# L_ftung_230217.net
KiCad netlist of a schematic drawn in EAGLE
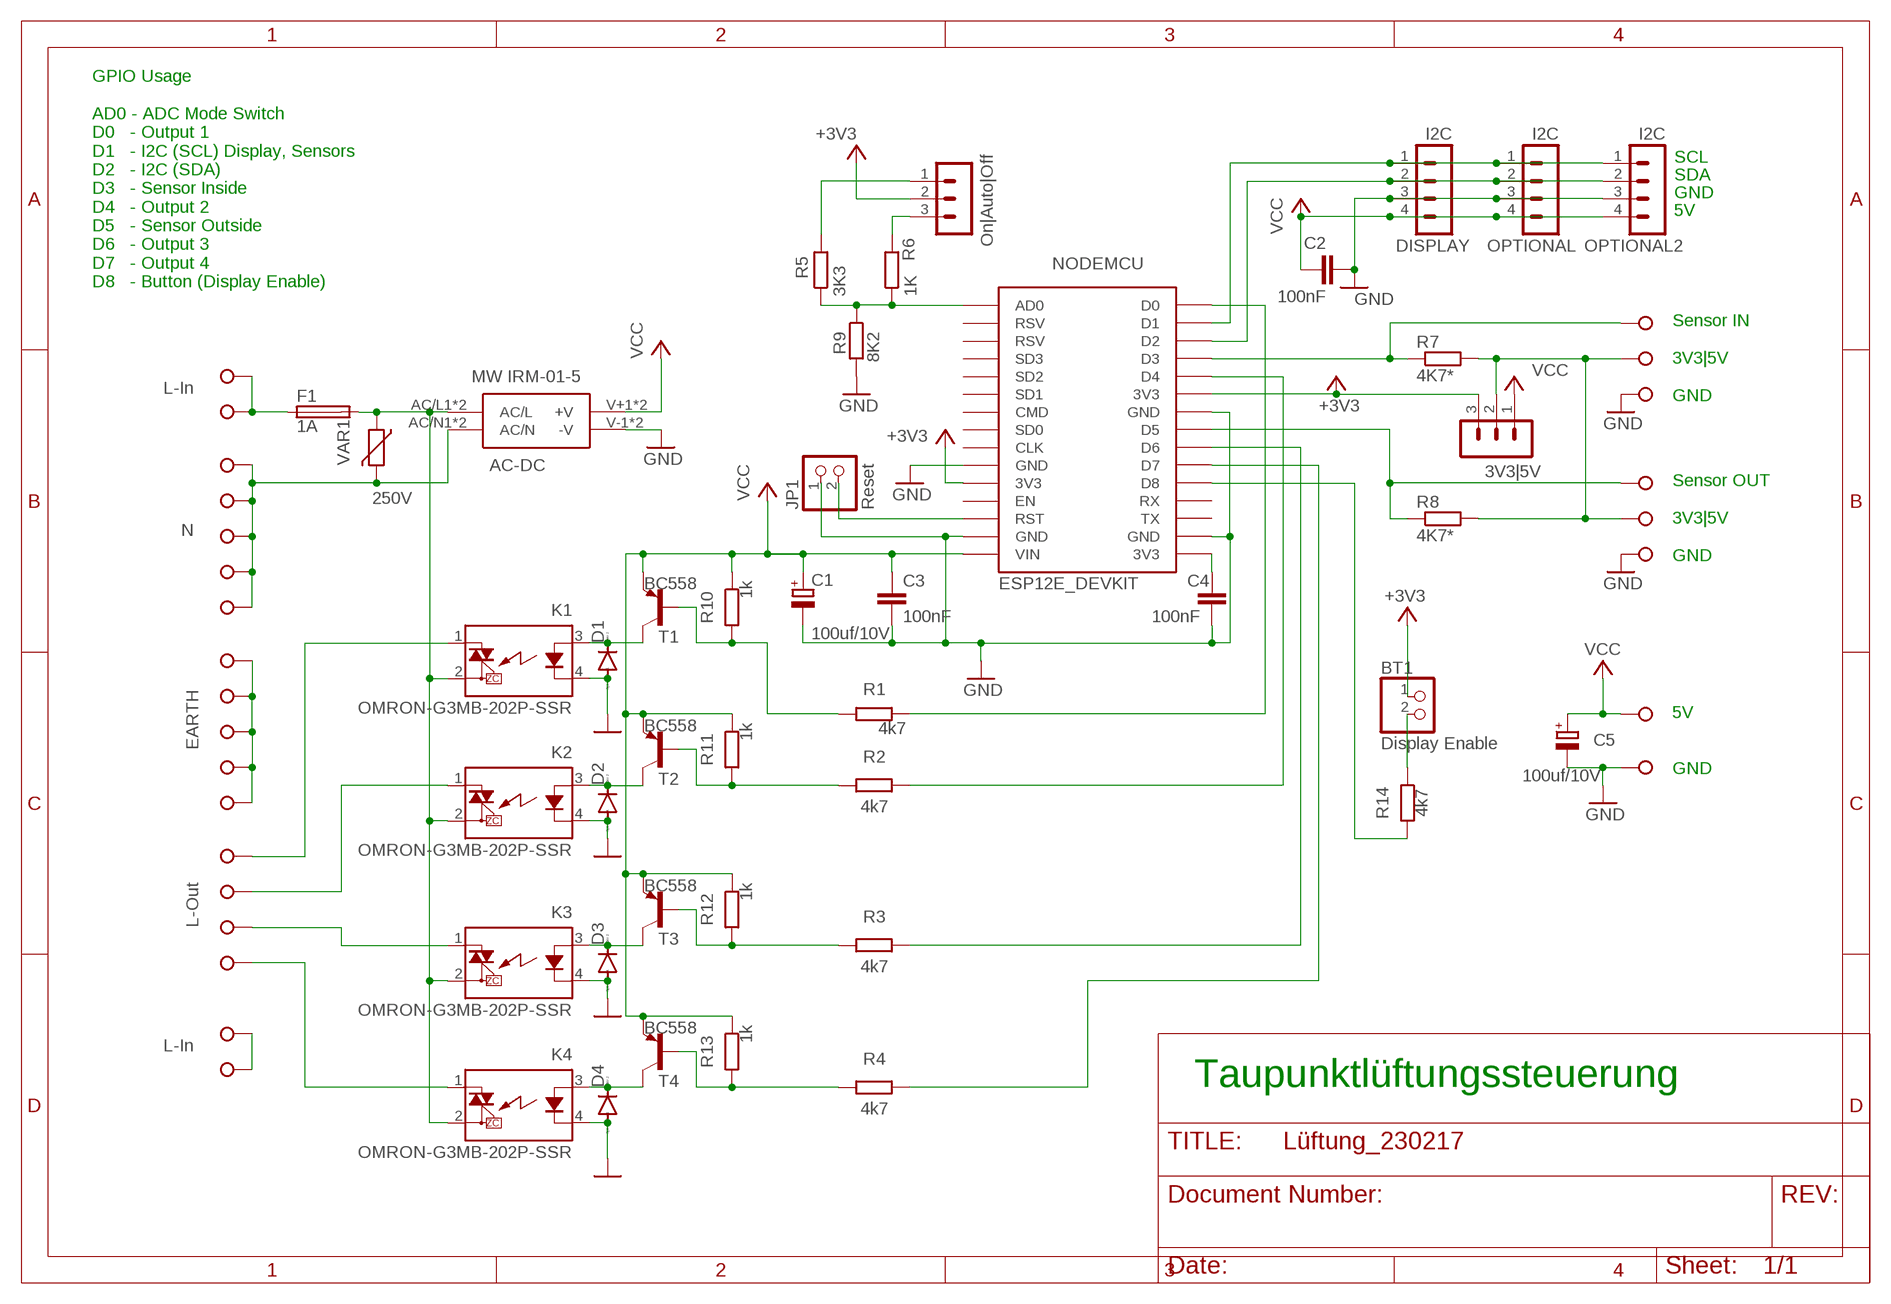
[diagram p0: schematic, sheet 1]

(export (version "E")
  (design (tool "Eeschema 10.0.6"))
  (components
    (comp (ref "5V|3V3")
      (value "3V3|5V")
      (footprint "eagle-import:LüFTUNG_230217_2_CON-LSTB_MA03-1")
      (libsource (lib "eagle-import") (part "LüFTUNG_230217_2_CON-LSTB_MA03-1"))
    )
    (comp (ref "AC-DC")
      (value "MW IRM-01-5")
      (footprint "eagle-import:LüFTUNG_230217_2_SAMACSYS_PARTS_IRM015")
      (fields
        (field (name "MANUFACTURER_PART_NUMBER") "IRM-01-5")
        (field (name "MOUSER_PART_NUMBER") "709-IRM01-5")
      )
      (libsource (lib "eagle-import") (part "LüFTUNG_230217_2_SAMACSYS_PARTS_IRM-01-5"))
    )
    (comp (ref "BT1")
      (value "Display Enable")
      (footprint "eagle-import:LüFTUNG_230217_2_PINHEAD_1X02")
      (libsource (lib "eagle-import") (part "LüFTUNG_230217_2_PINHEAD_PINHD-1X2"))
    )
    (comp (ref "C1")
      (value "100uf/10V")
      (footprint "eagle-import:LüFTUNG_230217_2_MY_RCL_E2,5-7")
      (libsource (lib "eagle-import") (part "LüFTUNG_230217_2_MY_RCL_CPOL-EUE2.5-7"))
    )
    (comp (ref "C2")
      (value "100nF")
      (footprint "eagle-import:LüFTUNG_230217_2_CAPACITOR-WIMA_C5B3.5")
      (libsource (lib "eagle-import") (part "LüFTUNG_230217_2_CAPACITOR-WIMA_C5/3.5"))
    )
    (comp (ref "C3")
      (value "100nF")
      (footprint "eagle-import:LüFTUNG_230217_2_CAPACITOR-WIMA_C5B3.5")
      (libsource (lib "eagle-import") (part "LüFTUNG_230217_2_CAPACITOR-WIMA_C5/3.5"))
    )
    (comp (ref "C4")
      (value "100nF")
      (footprint "eagle-import:LüFTUNG_230217_2_CAPACITOR-WIMA_C5B3.5")
      (libsource (lib "eagle-import") (part "LüFTUNG_230217_2_CAPACITOR-WIMA_C5/3.5"))
    )
    (comp (ref "C5")
      (value "100uf/10V")
      (footprint "eagle-import:LüFTUNG_230217_2_MY_RCL_E2,5-7")
      (libsource (lib "eagle-import") (part "LüFTUNG_230217_2_MY_RCL_CPOL-EUE2.5-7"))
    )
    (comp (ref "D1")
      (value "LüFTUNG_230217_2_DIODE_1N4148")
      (footprint "eagle-import:LüFTUNG_230217_2_DIODE_D-5")
      (libsource (lib "eagle-import") (part "LüFTUNG_230217_2_DIODE_1N4148"))
    )
    (comp (ref "D2")
      (value "LüFTUNG_230217_2_DIODE_1N4148DO35-7")
      (footprint "eagle-import:LüFTUNG_230217_2_DIODE_DO35-7")
      (libsource (lib "eagle-import") (part "LüFTUNG_230217_2_DIODE_1N4148DO35-7"))
    )
    (comp (ref "D3")
      (value "LüFTUNG_230217_2_DIODE_1N4148DO35-7")
      (footprint "eagle-import:LüFTUNG_230217_2_DIODE_DO35-7")
      (libsource (lib "eagle-import") (part "LüFTUNG_230217_2_DIODE_1N4148DO35-7"))
    )
    (comp (ref "D4")
      (value "LüFTUNG_230217_2_DIODE_1N4148DO35-7")
      (footprint "eagle-import:LüFTUNG_230217_2_DIODE_DO35-7")
      (libsource (lib "eagle-import") (part "LüFTUNG_230217_2_DIODE_1N4148DO35-7"))
    )
    (comp (ref "DISPLAY")
      (value "I2C")
      (footprint "eagle-import:LüFTUNG_230217_2_CON-LSTB_MA04-1")
      (libsource (lib "eagle-import") (part "LüFTUNG_230217_2_CON-LSTB_MA04-1"))
    )
    (comp (ref "F1")
      (value "1A")
      (footprint "eagle-import:LüFTUNG_230217_2_MY_FUSE_SH22,5")
      (libsource (lib "eagle-import") (part "LüFTUNG_230217_2_MY_FUSE_FUSESH22,5"))
    )
    (comp (ref "JP1")
      (value "Reset")
      (footprint "eagle-import:LüFTUNG_230217_2_PINHEAD_1X02")
      (libsource (lib "eagle-import") (part "LüFTUNG_230217_2_PINHEAD_PINHD-1X2"))
    )
    (comp (ref "K1")
      (value "OMRON-G3MB-202P-SSR")
      (footprint "eagle-import:LüFTUNG_230217_2_OMRON-G3MB-202P-SSR_OMRON-G3MB-202P-SSR")
      (libsource (lib "eagle-import") (part "LüFTUNG_230217_2_OMRON-G3MB-202P-SSR_OMRON-G3MB-202P-SSR"))
    )
    (comp (ref "K2")
      (value "OMRON-G3MB-202P-SSR")
      (footprint "eagle-import:LüFTUNG_230217_2_OMRON-G3MB-202P-SSR_OMRON-G3MB-202P-SSR")
      (libsource (lib "eagle-import") (part "LüFTUNG_230217_2_OMRON-G3MB-202P-SSR_OMRON-G3MB-202P-SSR"))
    )
    (comp (ref "K3")
      (value "OMRON-G3MB-202P-SSR")
      (footprint "eagle-import:LüFTUNG_230217_2_OMRON-G3MB-202P-SSR_OMRON-G3MB-202P-SSR")
      (libsource (lib "eagle-import") (part "LüFTUNG_230217_2_OMRON-G3MB-202P-SSR_OMRON-G3MB-202P-SSR"))
    )
    (comp (ref "K4")
      (value "OMRON-G3MB-202P-SSR")
      (footprint "eagle-import:LüFTUNG_230217_2_OMRON-G3MB-202P-SSR_OMRON-G3MB-202P-SSR")
      (libsource (lib "eagle-import") (part "LüFTUNG_230217_2_OMRON-G3MB-202P-SSR_OMRON-G3MB-202P-SSR"))
    )
    (comp (ref "NODEMCU")
      (value "ESP12E_DEVKIT")
      (footprint "eagle-import:LüFTUNG_230217_2_ESP12E_DEVKIT_ESP12E_DEVKIT")
      (libsource (lib "eagle-import") (part "LüFTUNG_230217_2_ESP12E_DEVKIT_ESP12E_DEVKIT"))
    )
    (comp (ref "OPTIONAL")
      (value "I2C")
      (footprint "eagle-import:LüFTUNG_230217_2_CON-LSTB_MA04-1")
      (libsource (lib "eagle-import") (part "LüFTUNG_230217_2_CON-LSTB_MA04-1"))
    )
    (comp (ref "OPTIONAL2")
      (value "I2C")
      (footprint "eagle-import:LüFTUNG_230217_2_CON-LSTB_MA04-1")
      (libsource (lib "eagle-import") (part "LüFTUNG_230217_2_CON-LSTB_MA04-1"))
    )
    (comp (ref "R1")
      (value "4k7")
      (footprint "eagle-import:LüFTUNG_230217_2_MY_RCL_0207_10")
      (libsource (lib "eagle-import") (part "LüFTUNG_230217_2_MY_RCL_R-EU_0207/10"))
    )
    (comp (ref "R2")
      (value "4k7")
      (footprint "eagle-import:LüFTUNG_230217_2_MY_RCL_0207_10")
      (libsource (lib "eagle-import") (part "LüFTUNG_230217_2_MY_RCL_R-EU_0207/10"))
    )
    (comp (ref "R3")
      (value "4k7")
      (footprint "eagle-import:LüFTUNG_230217_2_MY_RCL_0207_10")
      (libsource (lib "eagle-import") (part "LüFTUNG_230217_2_MY_RCL_R-EU_0207/10"))
    )
    (comp (ref "R4")
      (value "4k7")
      (footprint "eagle-import:LüFTUNG_230217_2_MY_RCL_0207_10")
      (libsource (lib "eagle-import") (part "LüFTUNG_230217_2_MY_RCL_R-EU_0207/10"))
    )
    (comp (ref "R5")
      (value "3K3")
      (footprint "eagle-import:LüFTUNG_230217_2_MY_RCL_0204V")
      (libsource (lib "eagle-import") (part "LüFTUNG_230217_2_MY_RCL_R-EU_0204/2V"))
    )
    (comp (ref "R6")
      (value "1K")
      (footprint "eagle-import:LüFTUNG_230217_2_MY_RCL_0204V")
      (libsource (lib "eagle-import") (part "LüFTUNG_230217_2_MY_RCL_R-EU_0204/2V"))
    )
    (comp (ref "R7")
      (value "4K7*")
      (footprint "eagle-import:LüFTUNG_230217_2_MY_RCL_0207_10")
      (libsource (lib "eagle-import") (part "LüFTUNG_230217_2_MY_RCL_R-EU_0207/10"))
    )
    (comp (ref "R8")
      (value "4K7*")
      (footprint "eagle-import:LüFTUNG_230217_2_MY_RCL_0207_10")
      (libsource (lib "eagle-import") (part "LüFTUNG_230217_2_MY_RCL_R-EU_0207/10"))
    )
    (comp (ref "R9")
      (value "8K2")
      (footprint "eagle-import:LüFTUNG_230217_2_MY_RCL_0204V")
      (libsource (lib "eagle-import") (part "LüFTUNG_230217_2_MY_RCL_R-EU_0204/2V"))
    )
    (comp (ref "R10")
      (value "1k")
      (footprint "eagle-import:LüFTUNG_230217_2_MY_RCL_0207_10")
      (libsource (lib "eagle-import") (part "LüFTUNG_230217_2_MY_RCL_R-EU_0207/10"))
    )
    (comp (ref "R11")
      (value "1k")
      (footprint "eagle-import:LüFTUNG_230217_2_MY_RCL_0207_10")
      (libsource (lib "eagle-import") (part "LüFTUNG_230217_2_MY_RCL_R-EU_0207/10"))
    )
    (comp (ref "R12")
      (value "1k")
      (footprint "eagle-import:LüFTUNG_230217_2_MY_RCL_0207_10")
      (libsource (lib "eagle-import") (part "LüFTUNG_230217_2_MY_RCL_R-EU_0207/10"))
    )
    (comp (ref "R13")
      (value "1k")
      (footprint "eagle-import:LüFTUNG_230217_2_MY_RCL_0207_10")
      (libsource (lib "eagle-import") (part "LüFTUNG_230217_2_MY_RCL_R-EU_0207/10"))
    )
    (comp (ref "R14")
      (value "4k7")
      (footprint "eagle-import:LüFTUNG_230217_2_MY_RCL_0207_10")
      (libsource (lib "eagle-import") (part "LüFTUNG_230217_2_MY_RCL_R-EU_0207/10"))
    )
    (comp (ref "SWITCH")
      (value "On|Auto|Off")
      (footprint "eagle-import:LüFTUNG_230217_2_CON-LSTB_MA03-1")
      (libsource (lib "eagle-import") (part "LüFTUNG_230217_2_CON-LSTB_MA03-1"))
    )
    (comp (ref "T1")
      (value "BC558")
      (footprint "eagle-import:LüFTUNG_230217_2_TRANSISTOR-NEU-TO92_TO92")
      (libsource (lib "eagle-import") (part "LüFTUNG_230217_2_TRANSISTOR-NEU-TO92_-PNP-TO92"))
    )
    (comp (ref "T2")
      (value "BC558")
      (footprint "eagle-import:LüFTUNG_230217_2_TRANSISTOR-NEU-TO92_TO92")
      (libsource (lib "eagle-import") (part "LüFTUNG_230217_2_TRANSISTOR-NEU-TO92_-PNP-TO92"))
    )
    (comp (ref "T3")
      (value "BC558")
      (footprint "eagle-import:LüFTUNG_230217_2_TRANSISTOR-NEU-TO92_TO92")
      (libsource (lib "eagle-import") (part "LüFTUNG_230217_2_TRANSISTOR-NEU-TO92_-PNP-TO92"))
    )
    (comp (ref "T4")
      (value "BC558")
      (footprint "eagle-import:LüFTUNG_230217_2_TRANSISTOR-NEU-TO92_TO92")
      (libsource (lib "eagle-import") (part "LüFTUNG_230217_2_TRANSISTOR-NEU-TO92_-PNP-TO92"))
    )
    (comp (ref "VAR1")
      (value "250V")
      (footprint "eagle-import:LüFTUNG_230217_2_MY_VARISTOR_R-5")
      (libsource (lib "eagle-import") (part "LüFTUNG_230217_2_MY_VARISTOR_VARISTOR-5"))
    )
    (comp (ref "X1")
      (value "L-In")
      (footprint "eagle-import:CON-WAGO-508_W236-1")
      (libsource (lib "eagle-import") (part "CON-WAGO-508_W236-1"))
    )
    (comp (ref "X2")
      (value "L-In")
      (footprint "eagle-import:CON-WAGO-508_W236-NOCAP")
      (libsource (lib "eagle-import") (part "CON-WAGO-508_W236-1CON-WAGO-508_W236-NOCAP"))
    )
    (comp (ref "X3")
      (value "N")
      (footprint "eagle-import:CON-WAGO-508_W236-1")
      (libsource (lib "eagle-import") (part "CON-WAGO-508_W236-1"))
    )
    (comp (ref "X4")
      (value "N")
      (footprint "eagle-import:CON-WAGO-508_W236-NOCAP")
      (libsource (lib "eagle-import") (part "CON-WAGO-508_W236-1CON-WAGO-508_W236-NOCAP"))
    )
    (comp (ref "X5")
      (value "N")
      (footprint "eagle-import:CON-WAGO-508_W236-NOCAP")
      (libsource (lib "eagle-import") (part "CON-WAGO-508_W236-1CON-WAGO-508_W236-NOCAP"))
    )
    (comp (ref "X6")
      (value "N")
      (footprint "eagle-import:CON-WAGO-508_W236-NOCAP")
      (libsource (lib "eagle-import") (part "CON-WAGO-508_W236-1CON-WAGO-508_W236-NOCAP"))
    )
    (comp (ref "X7")
      (value "N")
      (footprint "eagle-import:CON-WAGO-508_W236-NOCAP")
      (libsource (lib "eagle-import") (part "CON-WAGO-508_W236-1CON-WAGO-508_W236-NOCAP"))
    )
    (comp (ref "X8")
      (value "EARTH")
      (footprint "eagle-import:CON-WAGO-508_W236-1")
      (libsource (lib "eagle-import") (part "CON-WAGO-508_W236-1"))
    )
    (comp (ref "X9")
      (value "EARTH")
      (footprint "eagle-import:CON-WAGO-508_W236-NOCAP")
      (libsource (lib "eagle-import") (part "CON-WAGO-508_W236-1CON-WAGO-508_W236-NOCAP"))
    )
    (comp (ref "X10")
      (value "EARTH")
      (footprint "eagle-import:CON-WAGO-508_W236-NOCAP")
      (libsource (lib "eagle-import") (part "CON-WAGO-508_W236-1CON-WAGO-508_W236-NOCAP"))
    )
    (comp (ref "X11")
      (value "EARTH")
      (footprint "eagle-import:CON-WAGO-508_W236-NOCAP")
      (libsource (lib "eagle-import") (part "CON-WAGO-508_W236-1CON-WAGO-508_W236-NOCAP"))
    )
    (comp (ref "X12")
      (value "EARTH")
      (footprint "eagle-import:CON-WAGO-508_W236-NOCAP")
      (libsource (lib "eagle-import") (part "CON-WAGO-508_W236-1CON-WAGO-508_W236-NOCAP"))
    )
    (comp (ref "X13")
      (value "L-Out")
      (footprint "eagle-import:CON-WAGO-508_W236-1")
      (libsource (lib "eagle-import") (part "CON-WAGO-508_W236-1"))
    )
    (comp (ref "X14")
      (value "L-Out")
      (footprint "eagle-import:CON-WAGO-508_W236-NOCAP")
      (libsource (lib "eagle-import") (part "CON-WAGO-508_W236-1CON-WAGO-508_W236-NOCAP"))
    )
    (comp (ref "X15")
      (value "L-Out")
      (footprint "eagle-import:CON-WAGO-508_W236-NOCAP")
      (libsource (lib "eagle-import") (part "CON-WAGO-508_W236-1CON-WAGO-508_W236-NOCAP"))
    )
    (comp (ref "X16")
      (value "L-Out")
      (footprint "eagle-import:CON-WAGO-508_W236-NOCAP")
      (libsource (lib "eagle-import") (part "CON-WAGO-508_W236-1CON-WAGO-508_W236-NOCAP"))
    )
    (comp (ref "X17")
      (value "L-In")
      (footprint "eagle-import:CON-WAGO-508_W236-NOCAP")
      (libsource (lib "eagle-import") (part "CON-WAGO-508_W236-1CON-WAGO-508_W236-NOCAP"))
    )
    (comp (ref "X18")
      (value "L-In")
      (footprint "eagle-import:CON-WAGO-508_W236-1")
      (libsource (lib "eagle-import") (part "CON-WAGO-508_W236-1"))
    )
    (comp (ref "X19")
      (value "Sensor-In")
      (footprint "eagle-import:CON-WAGO-508_W236-NOCAP")
      (libsource (lib "eagle-import") (part "CON-WAGO-508_W236-1CON-WAGO-508_W236-NOCAP"))
    )
    (comp (ref "X20")
      (value "3V3")
      (footprint "eagle-import:CON-WAGO-508_W236-NOCAP")
      (libsource (lib "eagle-import") (part "CON-WAGO-508_W236-1CON-WAGO-508_W236-NOCAP"))
    )
    (comp (ref "X21")
      (value "GND")
      (footprint "eagle-import:CON-WAGO-508_W236-1")
      (libsource (lib "eagle-import") (part "CON-WAGO-508_W236-1"))
    )
    (comp (ref "X22")
      (value "Sensor-Out")
      (footprint "eagle-import:CON-WAGO-508_W236-NOCAP")
      (libsource (lib "eagle-import") (part "CON-WAGO-508_W236-1CON-WAGO-508_W236-NOCAP"))
    )
    (comp (ref "X23")
      (value "3V3")
      (footprint "eagle-import:CON-WAGO-508_W236-NOCAP")
      (libsource (lib "eagle-import") (part "CON-WAGO-508_W236-1CON-WAGO-508_W236-NOCAP"))
    )
    (comp (ref "X24")
      (value "GND")
      (footprint "eagle-import:CON-WAGO-508_W236-1")
      (libsource (lib "eagle-import") (part "CON-WAGO-508_W236-1"))
    )
    (comp (ref "X25")
      (value "GND")
      (footprint "eagle-import:CON-WAGO-508_W236-NOCAP")
      (libsource (lib "eagle-import") (part "CON-WAGO-508_W236-1CON-WAGO-508_W236-NOCAP"))
    )
    (comp (ref "X26")
      (value "VCC")
      (footprint "eagle-import:CON-WAGO-508_W236-1")
      (libsource (lib "eagle-import") (part "CON-WAGO-508_W236-1"))
    )
  )
  (nets
    (net (code "1") (name "+3V3") (class "Default")
      (node (ref "5V|3V3") (pin "3") (pinfunction "3_3") (pintype "passive"))
      (node (ref "BT1") (pin "1") (pinfunction "1_1") (pintype "passive"))
      (node (ref "NODEMCU") (pin "3V3@0") (pinfunction "3V3_3V3@0") (pintype "bidirectional"))
      (node (ref "NODEMCU") (pin "3V3@1") (pinfunction "3V3_3V3@1") (pintype "bidirectional"))
      (node (ref "SWITCH") (pin "2") (pinfunction "2_2") (pintype "passive"))
    )
    (net (code "2") (name "GND") (class "Default")
      (node (ref "AC-DC") (pin "V-1") (pinfunction "-V_V-1") (pintype "bidirectional"))
      (node (ref "AC-DC") (pin "V-2") (pinfunction "-V_V-2") (pintype "bidirectional"))
      (node (ref "C1") (pin "-") (pinfunction "-_-") (pintype "passive"))
      (node (ref "C2") (pin "2") (pinfunction "2_2") (pintype "passive"))
      (node (ref "C3") (pin "2") (pinfunction "2_2") (pintype "passive"))
      (node (ref "C4") (pin "2") (pinfunction "2_2") (pintype "passive"))
      (node (ref "C5") (pin "-") (pinfunction "-_-") (pintype "passive"))
      (node (ref "D1") (pin "A") (pinfunction "A_A") (pintype "passive"))
      (node (ref "D2") (pin "A") (pinfunction "A_A") (pintype "passive"))
      (node (ref "D3") (pin "A") (pinfunction "A_A") (pintype "passive"))
      (node (ref "D4") (pin "A") (pinfunction "A_A") (pintype "passive"))
      (node (ref "DISPLAY") (pin "3") (pinfunction "3_3") (pintype "passive"))
      (node (ref "JP1") (pin "1") (pinfunction "1_1") (pintype "passive"))
      (node (ref "K1") (pin "4") (pinfunction "K_4") (pintype "passive"))
      (node (ref "K2") (pin "4") (pinfunction "K_4") (pintype "passive"))
      (node (ref "K3") (pin "4") (pinfunction "K_4") (pintype "passive"))
      (node (ref "K4") (pin "4") (pinfunction "K_4") (pintype "passive"))
      (node (ref "NODEMCU") (pin "GND@0") (pinfunction "GND_GND@0") (pintype "bidirectional"))
      (node (ref "NODEMCU") (pin "GND@1") (pinfunction "GND_GND@1") (pintype "bidirectional"))
      (node (ref "NODEMCU") (pin "GND@2") (pinfunction "GND_GND@2") (pintype "bidirectional"))
      (node (ref "NODEMCU") (pin "GND@3") (pinfunction "GND_GND@3") (pintype "bidirectional"))
      (node (ref "OPTIONAL") (pin "3") (pinfunction "3_3") (pintype "passive"))
      (node (ref "OPTIONAL2") (pin "3") (pinfunction "3_3") (pintype "passive"))
      (node (ref "R9") (pin "2") (pinfunction "2_2") (pintype "passive"))
      (node (ref "X21") (pin "1") (pinfunction "KL1_1") (pintype "passive"))
      (node (ref "X21") (pin "2") (pinfunction "KL1_2") (pintype "passive"))
      (node (ref "X24") (pin "1") (pinfunction "KL1_1") (pintype "passive"))
      (node (ref "X24") (pin "2") (pinfunction "KL1_2") (pintype "passive"))
      (node (ref "X25") (pin "1") (pinfunction "KL1_1") (pintype "passive"))
      (node (ref "X25") (pin "2") (pinfunction "KL1_2") (pintype "passive"))
    )
    (net (code "3") (name "Net-(5V|3V3-Pad2)") (class "Default")
      (node (ref "5V|3V3") (pin "2") (pinfunction "2_2") (pintype "passive"))
      (node (ref "R7") (pin "2") (pinfunction "2_2") (pintype "passive"))
      (node (ref "R8") (pin "2") (pinfunction "2_2") (pintype "passive"))
      (node (ref "X20") (pin "1") (pinfunction "KL1_1") (pintype "passive"))
      (node (ref "X20") (pin "2") (pinfunction "KL1_2") (pintype "passive"))
      (node (ref "X23") (pin "1") (pinfunction "KL1_1") (pintype "passive"))
      (node (ref "X23") (pin "2") (pinfunction "KL1_2") (pintype "passive"))
    )
    (net (code "4") (name "Net-(AC-DC-AC{slash}N-PadAC{slash}N1)") (class "Default")
      (node (ref "AC-DC") (pin "AC/N1") (pinfunction "AC/N_AC/N1") (pintype "bidirectional"))
      (node (ref "AC-DC") (pin "AC/N2") (pinfunction "AC/N_AC/N2") (pintype "bidirectional"))
      (node (ref "VAR1") (pin "2") (pinfunction "2_2") (pintype "passive"))
      (node (ref "X3") (pin "1") (pinfunction "KL1_1") (pintype "passive"))
      (node (ref "X3") (pin "2") (pinfunction "KL1_2") (pintype "passive"))
      (node (ref "X4") (pin "1") (pinfunction "KL1_1") (pintype "passive"))
      (node (ref "X4") (pin "2") (pinfunction "KL1_2") (pintype "passive"))
      (node (ref "X5") (pin "1") (pinfunction "KL1_1") (pintype "passive"))
      (node (ref "X5") (pin "2") (pinfunction "KL1_2") (pintype "passive"))
      (node (ref "X6") (pin "1") (pinfunction "KL1_1") (pintype "passive"))
      (node (ref "X6") (pin "2") (pinfunction "KL1_2") (pintype "passive"))
      (node (ref "X7") (pin "1") (pinfunction "KL1_1") (pintype "passive"))
      (node (ref "X7") (pin "2") (pinfunction "KL1_2") (pintype "passive"))
    )
    (net (code "5") (name "Net-(BT1-Pad2)") (class "Default")
      (node (ref "BT1") (pin "2") (pinfunction "2_2") (pintype "passive"))
      (node (ref "R14") (pin "1") (pinfunction "1_1") (pintype "passive"))
    )
    (net (code "6") (name "Net-(C4-Pad1)") (class "Default")
      (node (ref "C4") (pin "1") (pinfunction "1_1") (pintype "passive"))
      (node (ref "NODEMCU") (pin "3V3@2") (pinfunction "3V3_3V3@2") (pintype "bidirectional"))
    )
    (net (code "7") (name "Net-(DISPLAY-Pad1)") (class "Default")
      (node (ref "DISPLAY") (pin "1") (pinfunction "1_1") (pintype "passive"))
      (node (ref "NODEMCU") (pin "D1") (pinfunction "D1_D1") (pintype "bidirectional"))
      (node (ref "OPTIONAL") (pin "1") (pinfunction "1_1") (pintype "passive"))
      (node (ref "OPTIONAL2") (pin "1") (pinfunction "1_1") (pintype "passive"))
    )
    (net (code "8") (name "Net-(DISPLAY-Pad2)") (class "Default")
      (node (ref "DISPLAY") (pin "2") (pinfunction "2_2") (pintype "passive"))
      (node (ref "NODEMCU") (pin "D2") (pinfunction "D2_D2") (pintype "bidirectional"))
      (node (ref "OPTIONAL") (pin "2") (pinfunction "2_2") (pintype "passive"))
      (node (ref "OPTIONAL2") (pin "2") (pinfunction "2_2") (pintype "passive"))
    )
    (net (code "9") (name "Net-(F1-Pad1)") (class "Default")
      (node (ref "F1") (pin "1") (pinfunction "1_1") (pintype "passive"))
      (node (ref "X1") (pin "1") (pinfunction "KL1_1") (pintype "passive"))
      (node (ref "X1") (pin "2") (pinfunction "KL1_2") (pintype "passive"))
      (node (ref "X2") (pin "1") (pinfunction "KL1_1") (pintype "passive"))
      (node (ref "X2") (pin "2") (pinfunction "KL1_2") (pintype "passive"))
    )
    (net (code "10") (name "Net-(JP1-Pad2)") (class "Default")
      (node (ref "JP1") (pin "2") (pinfunction "2_2") (pintype "passive"))
      (node (ref "NODEMCU") (pin "RST") (pinfunction "RST_RST") (pintype "bidirectional"))
    )
    (net (code "11") (name "Net-(K1-A)") (class "Default")
      (node (ref "D1") (pin "C") (pinfunction "C_C") (pintype "passive"))
      (node (ref "K1") (pin "3") (pinfunction "A_3") (pintype "passive"))
      (node (ref "T1") (pin "3") (pinfunction "C_3") (pintype "passive"))
    )
    (net (code "12") (name "Net-(K1-DS1)") (class "Default")
      (node (ref "K1") (pin "1") (pinfunction "DS1_1") (pintype "passive"))
      (node (ref "X13") (pin "1") (pinfunction "KL1_1") (pintype "passive"))
      (node (ref "X13") (pin "2") (pinfunction "KL1_2") (pintype "passive"))
    )
    (net (code "13") (name "Net-(K1-DS2)") (class "Default")
      (node (ref "AC-DC") (pin "AC/L1") (pinfunction "AC/L_AC/L1") (pintype "bidirectional"))
      (node (ref "AC-DC") (pin "AC/L2") (pinfunction "AC/L_AC/L2") (pintype "bidirectional"))
      (node (ref "F1") (pin "2") (pinfunction "2_2") (pintype "passive"))
      (node (ref "K1") (pin "2") (pinfunction "DS2_2") (pintype "passive"))
      (node (ref "K2") (pin "2") (pinfunction "DS2_2") (pintype "passive"))
      (node (ref "K3") (pin "2") (pinfunction "DS2_2") (pintype "passive"))
      (node (ref "K4") (pin "2") (pinfunction "DS2_2") (pintype "passive"))
      (node (ref "VAR1") (pin "1") (pinfunction "1_1") (pintype "passive"))
    )
    (net (code "14") (name "Net-(K2-A)") (class "Default")
      (node (ref "D2") (pin "C") (pinfunction "C_C") (pintype "passive"))
      (node (ref "K2") (pin "3") (pinfunction "A_3") (pintype "passive"))
      (node (ref "T2") (pin "3") (pinfunction "C_3") (pintype "passive"))
    )
    (net (code "15") (name "Net-(K2-DS1)") (class "Default")
      (node (ref "K2") (pin "1") (pinfunction "DS1_1") (pintype "passive"))
      (node (ref "X14") (pin "1") (pinfunction "KL1_1") (pintype "passive"))
      (node (ref "X14") (pin "2") (pinfunction "KL1_2") (pintype "passive"))
    )
    (net (code "16") (name "Net-(K3-A)") (class "Default")
      (node (ref "D3") (pin "C") (pinfunction "C_C") (pintype "passive"))
      (node (ref "K3") (pin "3") (pinfunction "A_3") (pintype "passive"))
      (node (ref "T3") (pin "3") (pinfunction "C_3") (pintype "passive"))
    )
    (net (code "17") (name "Net-(K3-DS1)") (class "Default")
      (node (ref "K3") (pin "1") (pinfunction "DS1_1") (pintype "passive"))
      (node (ref "X15") (pin "1") (pinfunction "KL1_1") (pintype "passive"))
      (node (ref "X15") (pin "2") (pinfunction "KL1_2") (pintype "passive"))
    )
    (net (code "18") (name "Net-(K4-A)") (class "Default")
      (node (ref "D4") (pin "C") (pinfunction "C_C") (pintype "passive"))
      (node (ref "K4") (pin "3") (pinfunction "A_3") (pintype "passive"))
      (node (ref "T4") (pin "3") (pinfunction "C_3") (pintype "passive"))
    )
    (net (code "19") (name "Net-(K4-DS1)") (class "Default")
      (node (ref "K4") (pin "1") (pinfunction "DS1_1") (pintype "passive"))
      (node (ref "X16") (pin "1") (pinfunction "KL1_1") (pintype "passive"))
      (node (ref "X16") (pin "2") (pinfunction "KL1_2") (pintype "passive"))
    )
    (net (code "20") (name "Net-(NODEMCU-PadAD0)") (class "Default")
      (node (ref "NODEMCU") (pin "AD0") (pinfunction "AD0_AD0") (pintype "bidirectional"))
      (node (ref "R5") (pin "1") (pinfunction "1_1") (pintype "passive"))
      (node (ref "R6") (pin "1") (pinfunction "1_1") (pintype "passive"))
      (node (ref "R9") (pin "1") (pinfunction "1_1") (pintype "passive"))
    )
    (net (code "21") (name "Net-(NODEMCU-PadD0)") (class "Default")
      (node (ref "NODEMCU") (pin "D0") (pinfunction "D0_D0") (pintype "bidirectional"))
      (node (ref "R1") (pin "1") (pinfunction "1_1") (pintype "passive"))
    )
    (net (code "22") (name "Net-(NODEMCU-PadD3)") (class "Default")
      (node (ref "NODEMCU") (pin "D3") (pinfunction "D3_D3") (pintype "bidirectional"))
      (node (ref "R7") (pin "1") (pinfunction "1_1") (pintype "passive"))
      (node (ref "X19") (pin "1") (pinfunction "KL1_1") (pintype "passive"))
      (node (ref "X19") (pin "2") (pinfunction "KL1_2") (pintype "passive"))
    )
    (net (code "23") (name "Net-(NODEMCU-PadD4)") (class "Default")
      (node (ref "NODEMCU") (pin "D4") (pinfunction "D4_D4") (pintype "bidirectional"))
      (node (ref "R2") (pin "1") (pinfunction "1_1") (pintype "passive"))
    )
    (net (code "24") (name "Net-(NODEMCU-PadD5)") (class "Default")
      (node (ref "NODEMCU") (pin "D5") (pinfunction "D5_D5") (pintype "bidirectional"))
      (node (ref "R8") (pin "1") (pinfunction "1_1") (pintype "passive"))
      (node (ref "X22") (pin "1") (pinfunction "KL1_1") (pintype "passive"))
      (node (ref "X22") (pin "2") (pinfunction "KL1_2") (pintype "passive"))
    )
    (net (code "25") (name "Net-(NODEMCU-PadD6)") (class "Default")
      (node (ref "NODEMCU") (pin "D6") (pinfunction "D6_D6") (pintype "bidirectional"))
      (node (ref "R3") (pin "1") (pinfunction "1_1") (pintype "passive"))
    )
    (net (code "26") (name "Net-(NODEMCU-PadD7)") (class "Default")
      (node (ref "NODEMCU") (pin "D7") (pinfunction "D7_D7") (pintype "bidirectional"))
      (node (ref "R4") (pin "1") (pinfunction "1_1") (pintype "passive"))
    )
    (net (code "27") (name "Net-(NODEMCU-PadD8)") (class "Default")
      (node (ref "NODEMCU") (pin "D8") (pinfunction "D8_D8") (pintype "bidirectional"))
      (node (ref "R14") (pin "2") (pinfunction "2_2") (pintype "passive"))
    )
    (net (code "28") (name "Net-(R5-Pad2)") (class "Default")
      (node (ref "R5") (pin "2") (pinfunction "2_2") (pintype "passive"))
      (node (ref "SWITCH") (pin "1") (pinfunction "1_1") (pintype "passive"))
    )
    (net (code "29") (name "Net-(R6-Pad2)") (class "Default")
      (node (ref "R6") (pin "2") (pinfunction "2_2") (pintype "passive"))
      (node (ref "SWITCH") (pin "3") (pinfunction "3_3") (pintype "passive"))
    )
    (net (code "30") (name "Net-(T1-B)") (class "Default")
      (node (ref "R1") (pin "2") (pinfunction "2_2") (pintype "passive"))
      (node (ref "R10") (pin "2") (pinfunction "2_2") (pintype "passive"))
      (node (ref "T1") (pin "2") (pinfunction "B_2") (pintype "passive"))
    )
    (net (code "31") (name "Net-(T2-B)") (class "Default")
      (node (ref "R11") (pin "2") (pinfunction "2_2") (pintype "passive"))
      (node (ref "R2") (pin "2") (pinfunction "2_2") (pintype "passive"))
      (node (ref "T2") (pin "2") (pinfunction "B_2") (pintype "passive"))
    )
    (net (code "32") (name "Net-(T3-B)") (class "Default")
      (node (ref "R12") (pin "2") (pinfunction "2_2") (pintype "passive"))
      (node (ref "R3") (pin "2") (pinfunction "2_2") (pintype "passive"))
      (node (ref "T3") (pin "2") (pinfunction "B_2") (pintype "passive"))
    )
    (net (code "33") (name "Net-(T4-B)") (class "Default")
      (node (ref "R13") (pin "2") (pinfunction "2_2") (pintype "passive"))
      (node (ref "R4") (pin "2") (pinfunction "2_2") (pintype "passive"))
      (node (ref "T4") (pin "2") (pinfunction "B_2") (pintype "passive"))
    )
    (net (code "34") (name "Net-(X10-KL1-Pad1)") (class "Default")
      (node (ref "X10") (pin "1") (pinfunction "KL1_1") (pintype "passive"))
      (node (ref "X10") (pin "2") (pinfunction "KL1_2") (pintype "passive"))
      (node (ref "X11") (pin "1") (pinfunction "KL1_1") (pintype "passive"))
      (node (ref "X11") (pin "2") (pinfunction "KL1_2") (pintype "passive"))
      (node (ref "X12") (pin "1") (pinfunction "KL1_1") (pintype "passive"))
      (node (ref "X12") (pin "2") (pinfunction "KL1_2") (pintype "passive"))
      (node (ref "X8") (pin "1") (pinfunction "KL1_1") (pintype "passive"))
      (node (ref "X8") (pin "2") (pinfunction "KL1_2") (pintype "passive"))
      (node (ref "X9") (pin "1") (pinfunction "KL1_1") (pintype "passive"))
      (node (ref "X9") (pin "2") (pinfunction "KL1_2") (pintype "passive"))
    )
    (net (code "35") (name "Net-(X17-KL1-Pad1)") (class "Default")
      (node (ref "X17") (pin "1") (pinfunction "KL1_1") (pintype "passive"))
      (node (ref "X17") (pin "2") (pinfunction "KL1_2") (pintype "passive"))
      (node (ref "X18") (pin "1") (pinfunction "KL1_1") (pintype "passive"))
      (node (ref "X18") (pin "2") (pinfunction "KL1_2") (pintype "passive"))
    )
    (net (code "36") (name "VCC") (class "Default")
      (node (ref "5V|3V3") (pin "1") (pinfunction "1_1") (pintype "passive"))
      (node (ref "AC-DC") (pin "V+1") (pinfunction "+V_V+1") (pintype "bidirectional"))
      (node (ref "AC-DC") (pin "V+2") (pinfunction "+V_V+2") (pintype "bidirectional"))
      (node (ref "C1") (pin "+") (pinfunction "+_+") (pintype "passive"))
      (node (ref "C2") (pin "1") (pinfunction "1_1") (pintype "passive"))
      (node (ref "C3") (pin "1") (pinfunction "1_1") (pintype "passive"))
      (node (ref "C5") (pin "+") (pinfunction "+_+") (pintype "passive"))
      (node (ref "DISPLAY") (pin "4") (pinfunction "4_4") (pintype "passive"))
      (node (ref "NODEMCU") (pin "VIN") (pinfunction "VIN_VIN") (pintype "bidirectional"))
      (node (ref "OPTIONAL") (pin "4") (pinfunction "4_4") (pintype "passive"))
      (node (ref "OPTIONAL2") (pin "4") (pinfunction "4_4") (pintype "passive"))
      (node (ref "R10") (pin "1") (pinfunction "1_1") (pintype "passive"))
      (node (ref "R11") (pin "1") (pinfunction "1_1") (pintype "passive"))
      (node (ref "R12") (pin "1") (pinfunction "1_1") (pintype "passive"))
      (node (ref "R13") (pin "1") (pinfunction "1_1") (pintype "passive"))
      (node (ref "T1") (pin "1") (pinfunction "E_1") (pintype "passive"))
      (node (ref "T2") (pin "1") (pinfunction "E_1") (pintype "passive"))
      (node (ref "T3") (pin "1") (pinfunction "E_1") (pintype "passive"))
      (node (ref "T4") (pin "1") (pinfunction "E_1") (pintype "passive"))
      (node (ref "X26") (pin "1") (pinfunction "KL1_1") (pintype "passive"))
      (node (ref "X26") (pin "2") (pinfunction "KL1_2") (pintype "passive"))
    )
    (net (code "37") (name "unconnected-(NODEMCU-PadCLK)") (class "Default")
      (node (ref "NODEMCU") (pin "CLK") (pinfunction "CLK_CLK") (pintype "bidirectional"))
    )
    (net (code "38") (name "unconnected-(NODEMCU-PadCMD)") (class "Default")
      (node (ref "NODEMCU") (pin "CMD") (pinfunction "CMD_CMD") (pintype "bidirectional"))
    )
    (net (code "39") (name "unconnected-(NODEMCU-PadEN)") (class "Default")
      (node (ref "NODEMCU") (pin "EN") (pinfunction "EN_EN") (pintype "bidirectional"))
    )
    (net (code "40") (name "unconnected-(NODEMCU-PadRX)") (class "Default")
      (node (ref "NODEMCU") (pin "RX") (pinfunction "RX_RX") (pintype "bidirectional"))
    )
    (net (code "41") (name "unconnected-(NODEMCU-PadSD0)") (class "Default")
      (node (ref "NODEMCU") (pin "SD0") (pinfunction "SD0_SD0") (pintype "bidirectional"))
    )
    (net (code "42") (name "unconnected-(NODEMCU-PadSD1)") (class "Default")
      (node (ref "NODEMCU") (pin "SD1") (pinfunction "SD1_SD1") (pintype "bidirectional"))
    )
    (net (code "43") (name "unconnected-(NODEMCU-PadSD2)") (class "Default")
      (node (ref "NODEMCU") (pin "SD2") (pinfunction "SD2_SD2") (pintype "bidirectional"))
    )
    (net (code "44") (name "unconnected-(NODEMCU-PadSD3)") (class "Default")
      (node (ref "NODEMCU") (pin "SD3") (pinfunction "SD3_SD3") (pintype "bidirectional"))
    )
    (net (code "45") (name "unconnected-(NODEMCU-PadTX)") (class "Default")
      (node (ref "NODEMCU") (pin "TX") (pinfunction "TX_TX") (pintype "bidirectional"))
    )
    (net (code "46") (name "unconnected-(NODEMCU-RSV-PadRSV@0)") (class "Default")
      (node (ref "NODEMCU") (pin "RSV@0") (pinfunction "RSV_RSV@0") (pintype "bidirectional"))
    )
    (net (code "47") (name "unconnected-(NODEMCU-RSV-PadRSV@1)") (class "Default")
      (node (ref "NODEMCU") (pin "RSV@1") (pinfunction "RSV_RSV@1") (pintype "bidirectional"))
    )
  )
)
